# 02_Microcontroller.net
KiCad netlist of a schematic drawn in Altium Designer
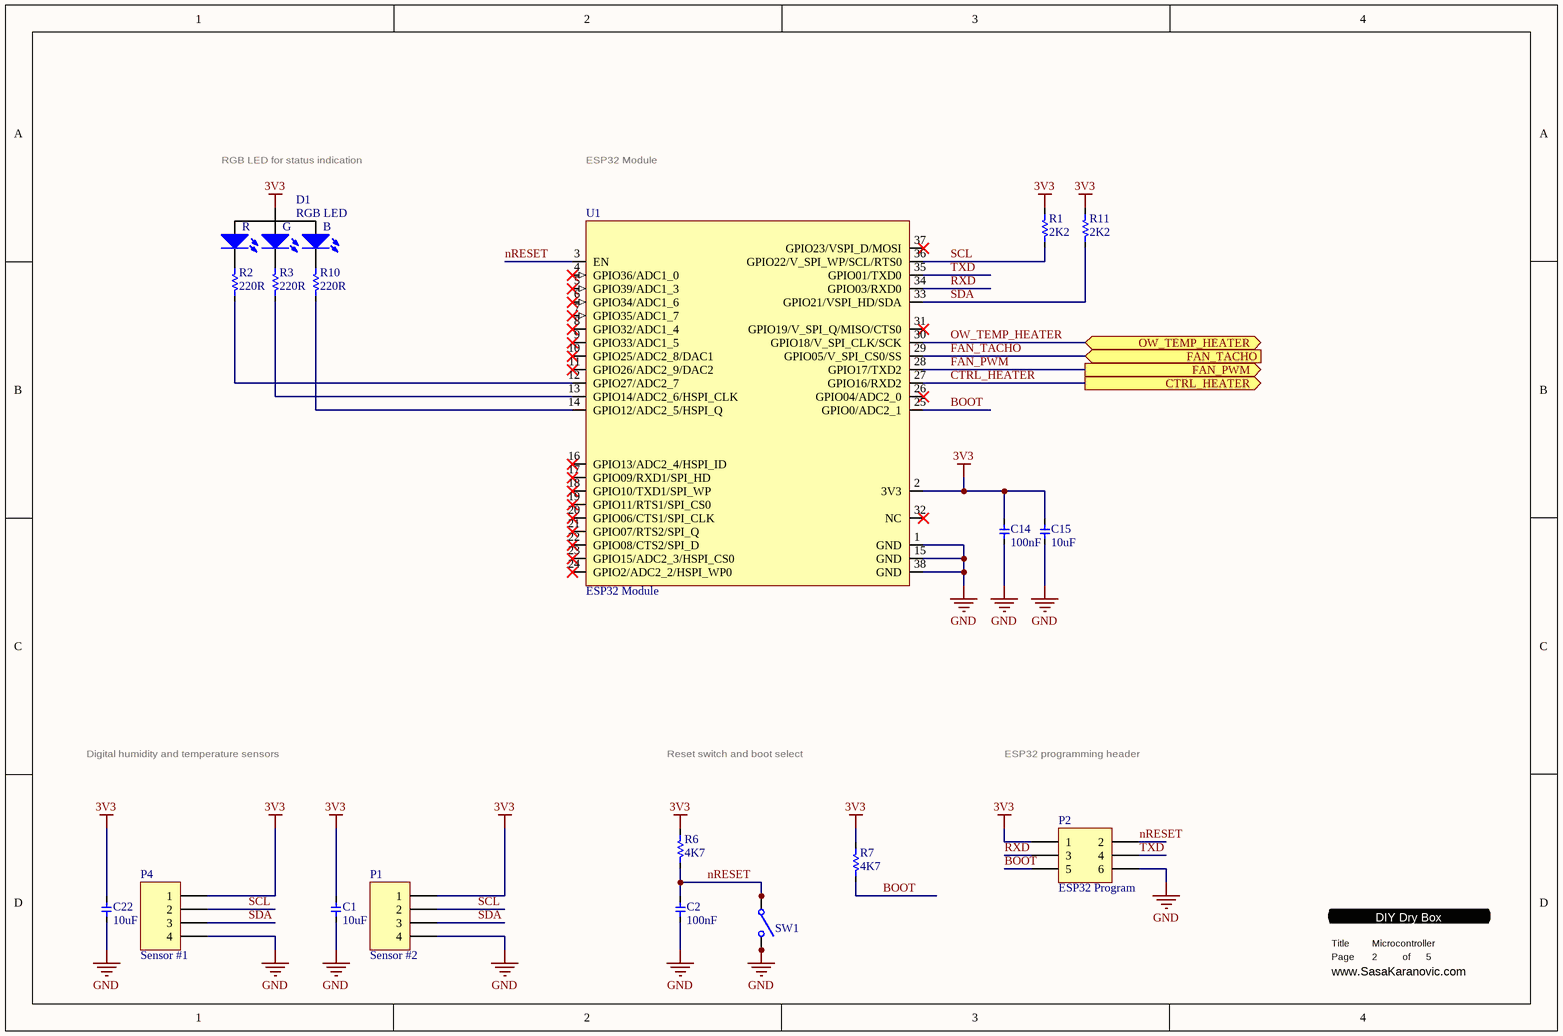
[diagram p0: 02_Microcontroller.SchDoc]

(export (version "E")
  (design (tool "Eeschema 10.0.6"))
  (components
    (comp (ref "C1")
      (value "10uF")
      (footprint "Moji Footprintovi:0603 - CAP HS")
      (description "Capacitor")
      (fields
        (field (name "MANUFACTURER") "Samsung Electro-Mechanics")
        (field (name "MANUFACTURER PART NUMBER") "CL10A106MO8NQNC")
      )
      (libsource (lib "Moji Schematici (1)") (part "Cap"))
    )
    (comp (ref "C2")
      (value "100nF")
      (footprint "Moji Footprintovi:0603 - CAP HS")
      (description "Capacitor")
      (fields
        (field (name "MANUFACTURER") "Samsung Electro-Mechanics")
        (field (name "MANUFACTURER PART NUMBER") "CL10B103KB8NNNC")
      )
      (libsource (lib "Moji Schematici (1)") (part "Cap"))
    )
    (comp (ref "C14")
      (value "100nF")
      (footprint "Moji Footprintovi:0603 - CAP HS")
      (description "Capacitor")
      (fields
        (field (name "MANUFACTURER") "Samsung Electro-Mechanics")
        (field (name "MANUFACTURER PART NUMBER") "CL10B103KB8NNNC")
      )
      (libsource (lib "Moji Schematici (1)") (part "Cap"))
    )
    (comp (ref "C15")
      (value "10uF")
      (footprint "Moji Footprintovi:0603 - CAP HS")
      (description "Capacitor")
      (fields
        (field (name "MANUFACTURER") "Samsung Electro-Mechanics")
        (field (name "MANUFACTURER PART NUMBER") "CL10A106MO8NQNC")
      )
      (libsource (lib "Moji Schematici (1)") (part "Cap"))
    )
    (comp (ref "C22")
      (value "10uF")
      (footprint "Moji Footprintovi:0603 - CAP HS")
      (description "Capacitor")
      (fields
        (field (name "MANUFACTURER") "Samsung Electro-Mechanics")
        (field (name "MANUFACTURER PART NUMBER") "CL10A106MO8NQNC")
      )
      (libsource (lib "Moji Schematici (1)") (part "Cap"))
    )
    (comp (ref "D1")
      (value "RGB LED")
      (footprint "hsbt_pcb:RGB LED - 0606 (1616 Metric)")
      (fields
        (field (name "MANUFACTURER") "Everlight Electronics Co Ltd")
        (field (name "MANUFACTURER PART NUMBER") "EAST1616RGBB2")
        (field (name "DISTRIBUTOR PART NUMBER") "1080-1551-1-ND")
      )
      (libsource (lib "hsbt_sch") (part "EAST1616RGBB2"))
    )
    (comp (ref "P1")
      (value "Sensor #2")
      (footprint "Moji Footprintovi:Header 4x1")
      (description "Header, 4-Pin")
      (libsource (lib "Schematic_Misc") (part "Header 4"))
    )
    (comp (ref "P2")
      (value "ESP32 Program")
      (footprint "HDR2X3")
      (description "Header, 3-Pin, Dual row")
      (libsource (lib "Miscellaneous Connectors") (part "Header 3X2"))
    )
    (comp (ref "P4")
      (value "Sensor #1")
      (footprint "Moji Footprintovi:Header 4x1")
      (description "Header, 4-Pin")
      (libsource (lib "Schematic_Misc") (part "Header 4"))
    )
    (comp (ref "R1")
      (value "2K2")
      (footprint "Footprint_Misc:0603 - HS")
      (description "Resistor")
      (fields
        (field (name "DISTRIBUTOR PART NUMBER") "RMCF0603JT2K20CT-ND")
        (field (name "MANUFACTURER") "Stackpole Electronics Inc")
      )
      (libsource (lib "Moji Schematici (1)") (part "Res"))
    )
    (comp (ref "R2")
      (value "220R")
      (footprint "Footprint_Misc:0603 - HS")
      (description "Resistor")
      (fields
        (field (name "DISTRIBUTOR PART NUMBER") "RMCF0603FT220RCT-ND")
        (field (name "MANUFACTURER") "Stackpole Electronics Inc")
      )
      (libsource (lib "Moji Schematici (1)") (part "Res"))
    )
    (comp (ref "R3")
      (value "220R")
      (footprint "Footprint_Misc:0603 - HS")
      (description "Resistor")
      (fields
        (field (name "DISTRIBUTOR PART NUMBER") "RMCF0603FT220RCT-ND")
        (field (name "MANUFACTURER") "Stackpole Electronics Inc")
      )
      (libsource (lib "Moji Schematici (1)") (part "Res"))
    )
    (comp (ref "R6")
      (value "4K7")
      (footprint "Footprint_Misc:0603 - HS")
      (description "Resistor")
      (fields
        (field (name "DISTRIBUTOR PART NUMBER") "RMCF0603FT4K70CT-ND")
        (field (name "MANUFACTURER") "Stackpole Electronics Inc")
      )
      (libsource (lib "Moji Schematici (1)") (part "Res"))
    )
    (comp (ref "R7")
      (value "4K7")
      (footprint "Footprint_Misc:0603 - HS")
      (description "Resistor")
      (fields
        (field (name "DISTRIBUTOR PART NUMBER") "RMCF0603FT4K70CT-ND")
        (field (name "MANUFACTURER") "Stackpole Electronics Inc")
      )
      (libsource (lib "Moji Schematici (1)") (part "Res"))
    )
    (comp (ref "R10")
      (value "220R")
      (footprint "Footprint_Misc:0603 - HS")
      (description "Resistor")
      (fields
        (field (name "DISTRIBUTOR PART NUMBER") "RMCF0603FT220RCT-ND")
        (field (name "MANUFACTURER") "Stackpole Electronics Inc")
      )
      (libsource (lib "Moji Schematici (1)") (part "Res"))
    )
    (comp (ref "R11")
      (value "2K2")
      (footprint "Footprint_Misc:0603 - HS")
      (description "Resistor")
      (fields
        (field (name "DISTRIBUTOR PART NUMBER") "RMCF0603JT2K20CT-ND")
        (field (name "MANUFACTURER") "Stackpole Electronics Inc")
      )
      (libsource (lib "Moji Schematici (1)") (part "Res"))
    )
    (comp (ref "SW1")
      (value "SWITCH TACTILE SPST-NO 0.05A 12V")
      (footprint "Moji Footprintovi:5mm_5mm_Switch_SMT")
      (fields
        (field (name "DISTRIBUTOR PART NUMBER") "CKN9088CT-ND")
        (field (name "MANUFACTURER") "C&K")
        (field (name "MANUFACTURER PART NUMBER") "PTS645SL50SMTR92 LFS")
      )
      (libsource (lib "Schematic_Misc") (part "PTS645SL50SMTR92 LFS"))
    )
    (comp (ref "U1")
      (value "ESP32 Module")
      (footprint "Footprint_Misc:ESP32-WROOM-32")
      (fields
        (field (name "MANUFACTURER PART NUMBER") "ESP32-WROOM-32D (4MB HIGH TEMP)")
        (field (name "MANUFACTURER") "Espressif Systems")
      )
      (libsource (lib "Schematic_Misc") (part "ESP32_Module"))
    )
  )
  (nets
    (net (code "1") (name "/BOOT") (class "Default")
      (node (ref "P2") (pin "5") (pinfunction "5_5") (pintype "passive"))
      (node (ref "R7") (pin "1") (pinfunction "1_1") (pintype "passive"))
      (node (ref "U1") (pin "25") (pinfunction "GPIO0/ADC2_1_25") (pintype "passive"))
    )
    (net (code "2") (name "/CTRL_HEATER") (class "Default")
      (node (ref "U1") (pin "27") (pinfunction "GPIO16/RXD2_27") (pintype "passive"))
    )
    (net (code "3") (name "/FAN_PWM") (class "Default")
      (node (ref "U1") (pin "28") (pinfunction "GPIO17/TXD2_28") (pintype "passive"))
    )
    (net (code "4") (name "/FAN_TACHO") (class "Default")
      (node (ref "U1") (pin "29") (pinfunction "GPIO05/V_SPI_CS0/SS_29") (pintype "passive"))
    )
    (net (code "5") (name "/OW_TEMP_HEATER") (class "Default")
      (node (ref "U1") (pin "30") (pinfunction "GPIO18/V_SPI_CLK/SCK_30") (pintype "passive"))
    )
    (net (code "6") (name "/RXD") (class "Default")
      (node (ref "P2") (pin "3") (pinfunction "3_3") (pintype "passive"))
      (node (ref "U1") (pin "34") (pinfunction "GPIO03/RXD0_34") (pintype "passive"))
    )
    (net (code "7") (name "/SCL") (class "Default")
      (node (ref "P1") (pin "2") (pinfunction "2_2") (pintype "passive"))
      (node (ref "P4") (pin "2") (pinfunction "2_2") (pintype "passive"))
      (node (ref "R1") (pin "1") (pinfunction "1_1") (pintype "passive"))
      (node (ref "U1") (pin "36") (pinfunction "GPIO22/V_SPI_WP/SCL/RTS0_36") (pintype "passive"))
    )
    (net (code "8") (name "/SDA") (class "Default")
      (node (ref "P1") (pin "3") (pinfunction "3_3") (pintype "passive"))
      (node (ref "P4") (pin "3") (pinfunction "3_3") (pintype "passive"))
      (node (ref "R11") (pin "1") (pinfunction "1_1") (pintype "passive"))
      (node (ref "U1") (pin "33") (pinfunction "GPIO21/VSPI_HD/SDA_33") (pintype "passive"))
    )
    (net (code "9") (name "/TXD") (class "Default")
      (node (ref "P2") (pin "4") (pinfunction "4_4") (pintype "passive"))
      (node (ref "U1") (pin "35") (pinfunction "GPIO01/TXD0_35") (pintype "passive"))
    )
    (net (code "10") (name "/nRESET") (class "Default")
      (node (ref "C2") (pin "1") (pinfunction "1_1") (pintype "passive"))
      (node (ref "P2") (pin "2") (pinfunction "2_2") (pintype "passive"))
      (node (ref "R6") (pin "1") (pinfunction "1_1") (pintype "passive"))
      (node (ref "SW1") (pin "1") (pinfunction "COMMON1_1") (pintype "passive"))
      (node (ref "SW1") (pin "2") (pinfunction "COMMON1_2") (pintype "passive"))
      (node (ref "U1") (pin "3") (pinfunction "EN_3") (pintype "passive"))
    )
    (net (code "11") (name "3V3") (class "Default")
      (node (ref "C1") (pin "1") (pinfunction "1_1") (pintype "passive"))
      (node (ref "C14") (pin "1") (pinfunction "1_1") (pintype "passive"))
      (node (ref "C15") (pin "1") (pinfunction "1_1") (pintype "passive"))
      (node (ref "C22") (pin "1") (pinfunction "1_1") (pintype "passive"))
      (node (ref "D1") (pin "4") (pinfunction "4_4") (pintype "passive"))
      (node (ref "P1") (pin "1") (pinfunction "1_1") (pintype "passive"))
      (node (ref "P2") (pin "1") (pinfunction "1_1") (pintype "passive"))
      (node (ref "P4") (pin "1") (pinfunction "1_1") (pintype "passive"))
      (node (ref "R1") (pin "2") (pinfunction "2_2") (pintype "passive"))
      (node (ref "R11") (pin "2") (pinfunction "2_2") (pintype "passive"))
      (node (ref "R6") (pin "2") (pinfunction "2_2") (pintype "passive"))
      (node (ref "R7") (pin "2") (pinfunction "2_2") (pintype "passive"))
      (node (ref "U1") (pin "2") (pinfunction "3V3_2") (pintype "passive"))
    )
    (net (code "12") (name "GND") (class "Default")
      (node (ref "C1") (pin "2") (pinfunction "2_2") (pintype "passive"))
      (node (ref "C14") (pin "2") (pinfunction "2_2") (pintype "passive"))
      (node (ref "C15") (pin "2") (pinfunction "2_2") (pintype "passive"))
      (node (ref "C2") (pin "2") (pinfunction "2_2") (pintype "passive"))
      (node (ref "C22") (pin "2") (pinfunction "2_2") (pintype "passive"))
      (node (ref "P1") (pin "4") (pinfunction "4_4") (pintype "passive"))
      (node (ref "P2") (pin "6") (pinfunction "6_6") (pintype "passive"))
      (node (ref "P4") (pin "4") (pinfunction "4_4") (pintype "passive"))
      (node (ref "SW1") (pin "3") (pinfunction "COMMON2_3") (pintype "passive"))
      (node (ref "SW1") (pin "4") (pinfunction "COMMON2_4") (pintype "passive"))
      (node (ref "U1") (pin "1") (pinfunction "GND_1") (pintype "passive"))
      (node (ref "U1") (pin "15") (pinfunction "GND_15") (pintype "passive"))
      (node (ref "U1") (pin "38") (pinfunction "GND_38") (pintype "passive"))
    )
    (net (code "13") (name "Net-(D1-Pad1)") (class "Default")
      (node (ref "D1") (pin "1") (pinfunction "1_1") (pintype "passive"))
      (node (ref "R2") (pin "2") (pinfunction "2_2") (pintype "passive"))
    )
    (net (code "14") (name "Net-(D1-Pad2)") (class "Default")
      (node (ref "D1") (pin "2") (pinfunction "2_2") (pintype "passive"))
      (node (ref "R3") (pin "2") (pinfunction "2_2") (pintype "passive"))
    )
    (net (code "15") (name "Net-(D1-Pad3)") (class "Default")
      (node (ref "D1") (pin "3") (pinfunction "3_3") (pintype "passive"))
      (node (ref "R10") (pin "2") (pinfunction "2_2") (pintype "passive"))
    )
    (net (code "16") (name "Net-(U1-GPIO12{slash}ADC2_5{slash}HSPI_Q)") (class "Default")
      (node (ref "R10") (pin "1") (pinfunction "1_1") (pintype "passive"))
      (node (ref "U1") (pin "14") (pinfunction "GPIO12/ADC2_5/HSPI_Q_14") (pintype "passive"))
    )
    (net (code "17") (name "Net-(U1-GPIO14{slash}ADC2_6{slash}HSPI_CLK)") (class "Default")
      (node (ref "R3") (pin "1") (pinfunction "1_1") (pintype "passive"))
      (node (ref "U1") (pin "13") (pinfunction "GPIO14/ADC2_6/HSPI_CLK_13") (pintype "passive"))
    )
    (net (code "18") (name "Net-(U1-GPIO27{slash}ADC2_7)") (class "Default")
      (node (ref "R2") (pin "1") (pinfunction "1_1") (pintype "passive"))
      (node (ref "U1") (pin "12") (pinfunction "GPIO27/ADC2_7_12") (pintype "passive"))
    )
    (net (code "19") (name "unconnected-(U1-GPIO2{slash}ADC2_2{slash}HSPI_WP0-Pad24)") (class "Default")
      (node (ref "U1") (pin "24") (pinfunction "GPIO2/ADC2_2/HSPI_WP0_24") (pintype "passive+no_connect"))
    )
    (net (code "20") (name "unconnected-(U1-GPIO04{slash}ADC2_0-Pad26)") (class "Default")
      (node (ref "U1") (pin "26") (pinfunction "GPIO04/ADC2_0_26") (pintype "passive+no_connect"))
    )
    (net (code "21") (name "unconnected-(U1-GPIO06{slash}CTS1{slash}SPI_CLK-Pad20)") (class "Default")
      (node (ref "U1") (pin "20") (pinfunction "GPIO06/CTS1/SPI_CLK_20") (pintype "passive+no_connect"))
    )
    (net (code "22") (name "unconnected-(U1-GPIO07{slash}RTS2{slash}SPI_Q-Pad21)") (class "Default")
      (node (ref "U1") (pin "21") (pinfunction "GPIO07/RTS2/SPI_Q_21") (pintype "passive+no_connect"))
    )
    (net (code "23") (name "unconnected-(U1-GPIO08{slash}CTS2{slash}SPI_D-Pad22)") (class "Default")
      (node (ref "U1") (pin "22") (pinfunction "GPIO08/CTS2/SPI_D_22") (pintype "passive+no_connect"))
    )
    (net (code "24") (name "unconnected-(U1-GPIO09{slash}RXD1{slash}SPI_HD-Pad17)") (class "Default")
      (node (ref "U1") (pin "17") (pinfunction "GPIO09/RXD1/SPI_HD_17") (pintype "passive+no_connect"))
    )
    (net (code "25") (name "unconnected-(U1-GPIO10{slash}TXD1{slash}SPI_WP-Pad18)") (class "Default")
      (node (ref "U1") (pin "18") (pinfunction "GPIO10/TXD1/SPI_WP_18") (pintype "passive+no_connect"))
    )
    (net (code "26") (name "unconnected-(U1-GPIO11{slash}RTS1{slash}SPI_CS0-Pad19)") (class "Default")
      (node (ref "U1") (pin "19") (pinfunction "GPIO11/RTS1/SPI_CS0_19") (pintype "passive+no_connect"))
    )
    (net (code "27") (name "unconnected-(U1-GPIO13{slash}ADC2_4{slash}HSPI_ID-Pad16)") (class "Default")
      (node (ref "U1") (pin "16") (pinfunction "GPIO13/ADC2_4/HSPI_ID_16") (pintype "passive+no_connect"))
    )
    (net (code "28") (name "unconnected-(U1-GPIO15{slash}ADC2_3{slash}HSPI_CS0-Pad23)") (class "Default")
      (node (ref "U1") (pin "23") (pinfunction "GPIO15/ADC2_3/HSPI_CS0_23") (pintype "passive+no_connect"))
    )
    (net (code "29") (name "unconnected-(U1-GPIO19{slash}V_SPI_Q{slash}MISO{slash}CTS0-Pad31)") (class "Default")
      (node (ref "U1") (pin "31") (pinfunction "GPIO19/V_SPI_Q/MISO/CTS0_31") (pintype "passive+no_connect"))
    )
    (net (code "30") (name "unconnected-(U1-GPIO23{slash}VSPI_D{slash}MOSI-Pad37)") (class "Default")
      (node (ref "U1") (pin "37") (pinfunction "GPIO23/VSPI_D/MOSI_37") (pintype "passive+no_connect"))
    )
    (net (code "31") (name "unconnected-(U1-GPIO25{slash}ADC2_8{slash}DAC1-Pad10)") (class "Default")
      (node (ref "U1") (pin "10") (pinfunction "GPIO25/ADC2_8/DAC1_10") (pintype "passive+no_connect"))
    )
    (net (code "32") (name "unconnected-(U1-GPIO26{slash}ADC2_9{slash}DAC2-Pad11)") (class "Default")
      (node (ref "U1") (pin "11") (pinfunction "GPIO26/ADC2_9/DAC2_11") (pintype "passive+no_connect"))
    )
    (net (code "33") (name "unconnected-(U1-GPIO32{slash}ADC1_4-Pad8)") (class "Default")
      (node (ref "U1") (pin "8") (pinfunction "GPIO32/ADC1_4_8") (pintype "passive+no_connect"))
    )
    (net (code "34") (name "unconnected-(U1-GPIO33{slash}ADC1_5-Pad9)") (class "Default")
      (node (ref "U1") (pin "9") (pinfunction "GPIO33/ADC1_5_9") (pintype "passive+no_connect"))
    )
    (net (code "35") (name "unconnected-(U1-GPIO34{slash}ADC1_6-Pad6)") (class "Default")
      (node (ref "U1") (pin "6") (pinfunction "GPIO34/ADC1_6_6") (pintype "input+no_connect"))
    )
    (net (code "36") (name "unconnected-(U1-GPIO35{slash}ADC1_7-Pad7)") (class "Default")
      (node (ref "U1") (pin "7") (pinfunction "GPIO35/ADC1_7_7") (pintype "input+no_connect"))
    )
    (net (code "37") (name "unconnected-(U1-GPIO36{slash}ADC1_0-Pad4)") (class "Default")
      (node (ref "U1") (pin "4") (pinfunction "GPIO36/ADC1_0_4") (pintype "input+no_connect"))
    )
    (net (code "38") (name "unconnected-(U1-GPIO39{slash}ADC1_3-Pad5)") (class "Default")
      (node (ref "U1") (pin "5") (pinfunction "GPIO39/ADC1_3_5") (pintype "input+no_connect"))
    )
    (net (code "39") (name "unconnected-(U1-NC-Pad32)") (class "Default")
      (node (ref "U1") (pin "32") (pinfunction "NC_32") (pintype "passive+no_connect"))
    )
  )
)
